# Fan.net
KiCad netlist of a schematic drawn in Altium Designer
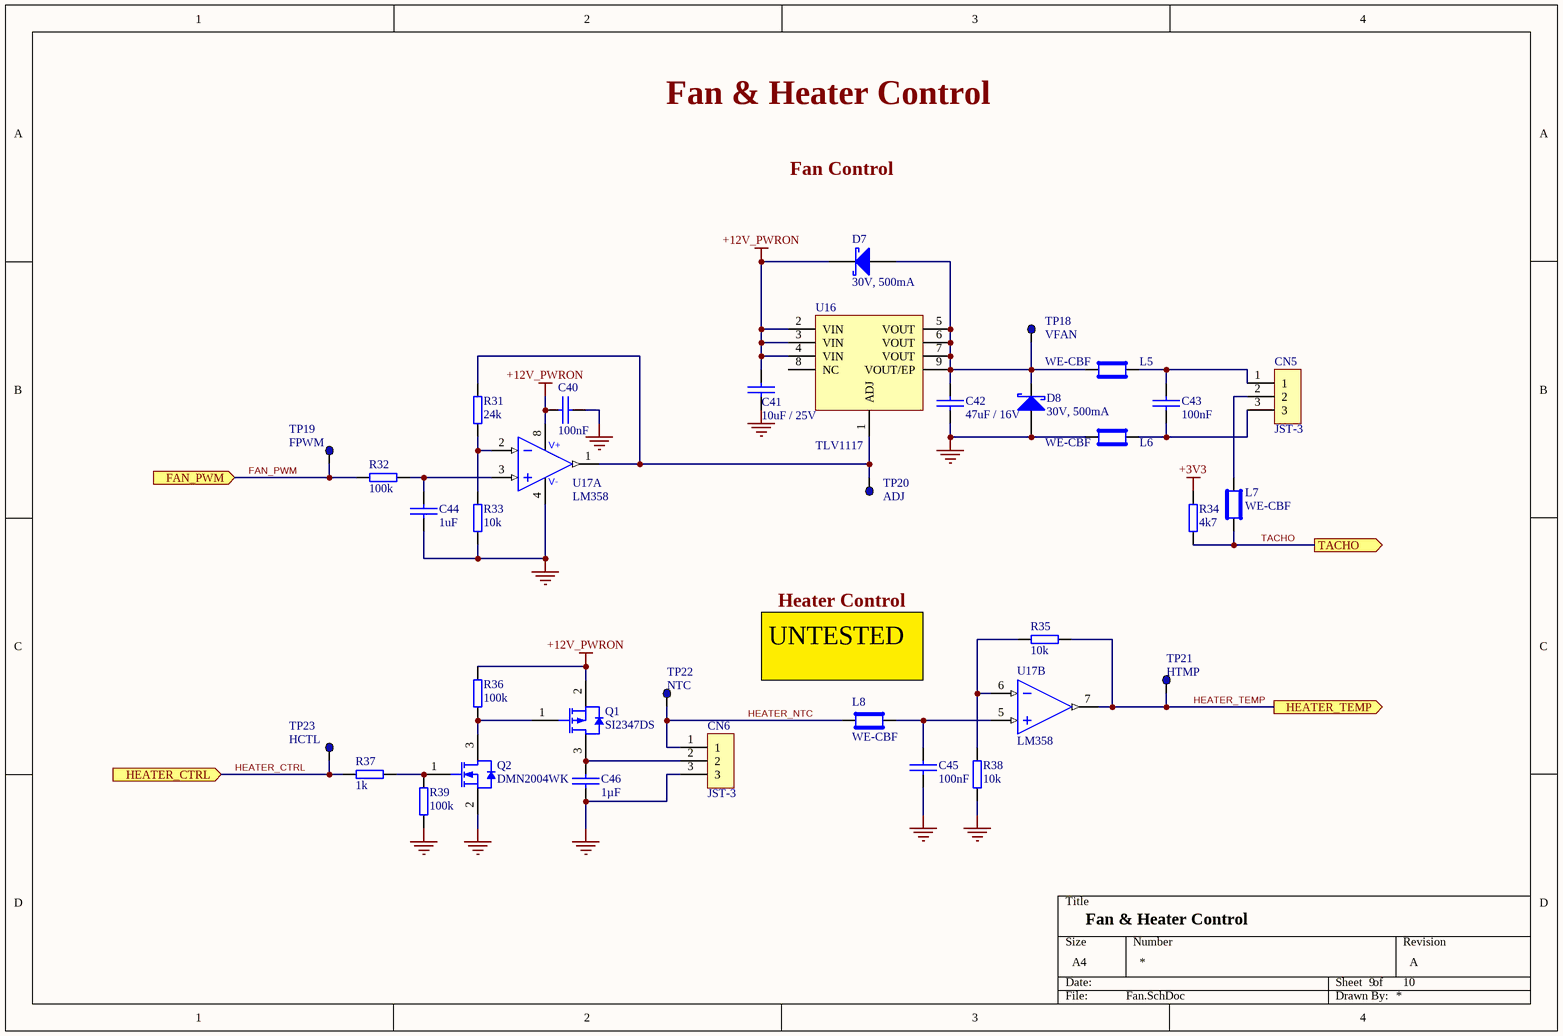
[diagram p0: Fan.SchDoc]

(export (version "E")
  (design (tool "Eeschema 10.0.6"))
  (components
    (comp (ref "C40")
      (value "100nF")
      (footprint "C0603")
      (description "CAP CER 0.1UF 50V X7R 0603")
      (fields (field (name "PART NUMBER") "C0603C104K5RACTU") (field (name "MANUFACTURER") "Kemet"))
      (libsource (lib "AKLib") (part "CAP"))
    )
    (comp (ref "C41")
      (value "10uF / 25V")
      (footprint "C0603")
      (description "CAP CER 10UF 25V X5R 0603")
      (fields
        (field (name "PART NUMBER") "ZRB18AR61E106ME01L")
        (field (name "MANUFACTURER") "Murata Electronics North America")
      )
      (libsource (lib "AKLib") (part "CAP"))
    )
    (comp (ref "C42")
      (value "47uF / 16V")
      (footprint "C1206")
      (description "CAP CER 47UF 16V X5R 1206")
      (fields
        (field (name "PART NUMBER") "C3216X5R1C476M160AB")
        (field (name "MANUFACTURER") "TDK Corporation")
      )
      (libsource (lib "AKLib") (part "CAP"))
    )
    (comp (ref "C43")
      (value "100nF")
      (footprint "C0603")
      (description "CAP CER 0.1UF 50V X7R 0603")
      (fields (field (name "PART NUMBER") "C0603C104K5RACTU") (field (name "MANUFACTURER") "Kemet"))
      (libsource (lib "AKLib") (part "CAP"))
    )
    (comp (ref "C44")
      (value "1uF")
      (footprint "C0603")
      (description "CAP CER 1UF 25V X7R 0603")
      (fields
        (field (name "PART NUMBER") "GCM188R71E105KA64D")
        (field (name "MANUFACTURER") "Murata Electronics North America")
      )
      (libsource (lib "AKLib") (part "CAP"))
    )
    (comp (ref "C45")
      (value "100nF")
      (footprint "C0603")
      (description "CAP CER 0.1UF 50V X7R 0603")
      (fields (field (name "PART NUMBER") "C0603C104K5RACTU") (field (name "MANUFACTURER") "Kemet"))
      (libsource (lib "AKLib") (part "CAP"))
    )
    (comp (ref "C46")
      (value "1µF")
      (footprint "C0805")
      (description "CAP CER 1UF 50V X7R 0805")
      (fields (field (name "PART NUMBER") "C0805C105K5RACTU") (field (name "MANUFACTURER") "Kemet"))
      (libsource (lib "AKLib") (part "CAP"))
    )
    (comp (ref "CN5")
      (value "JST-3")
      (footprint "JST-3")
      (description "CONN HEADER XH TOP 3POS 2.5MM")
      (fields
        (field (name "PART NUMBER") "B3B-XH-A(LF)(SN)")
        (field (name "MANUFACTURER") "JST Sales America Inc.")
      )
      (libsource (lib "AKLib") (part "Header 1x3"))
    )
    (comp (ref "CN6")
      (value "JST-3")
      (footprint "JST-3")
      (description "CONN HEADER XH TOP 3POS 2.5MM")
      (fields
        (field (name "PART NUMBER") "B3B-XH-A(LF)(SN)")
        (field (name "MANUFACTURER") "JST Sales America Inc.")
      )
      (libsource (lib "AKLib") (part "Header 1x3"))
    )
    (comp (ref "D7")
      (value "30V, 500mA")
      (footprint "SOD523_N")
      (description "DIODE SCHOTTKY 30V 500MA SC79-2")
      (fields
        (field (name "PART NUMBER") "BAS 3005B-02V H6327")
        (field (name "MANUFACTURER") "Infineon Technologies")
      )
      (libsource (lib "AKLib") (part "Schottky Diode"))
    )
    (comp (ref "D8")
      (value "30V, 500mA")
      (footprint "SOD523_N")
      (description "DIODE SCHOTTKY 30V 500MA SC79-2")
      (fields
        (field (name "PART NUMBER") "BAS 3005B-02V H6327")
        (field (name "MANUFACTURER") "Infineon Technologies")
      )
      (libsource (lib "AKLib") (part "Schottky Diode"))
    )
    (comp (ref "L5")
      (value "WE-CBF")
      (footprint "L0603")
      (description "FERRITE BEAD 600 OHM 0603 1LN")
      (fields (field (name "PART NUMBER") "742792651") (field (name "MANUFACTURER") "Wurth Electronics Inc."))
      (libsource (lib "AKLib") (part "FBEAD"))
    )
    (comp (ref "L6")
      (value "WE-CBF")
      (footprint "L0603")
      (description "FERRITE BEAD 600 OHM 0603 1LN")
      (fields (field (name "PART NUMBER") "742792651") (field (name "MANUFACTURER") "Wurth Electronics Inc."))
      (libsource (lib "AKLib") (part "FBEAD"))
    )
    (comp (ref "L7")
      (value "WE-CBF")
      (footprint "L0603")
      (description "FERRITE BEAD 600 OHM 0603 1LN")
      (fields (field (name "PART NUMBER") "742792651") (field (name "MANUFACTURER") "Wurth Electronics Inc."))
      (libsource (lib "AKLib") (part "FBEAD"))
    )
    (comp (ref "L8")
      (value "WE-CBF")
      (footprint "L0603")
      (description "FERRITE BEAD 600 OHM 0603 1LN")
      (fields (field (name "PART NUMBER") "742792651") (field (name "MANUFACTURER") "Wurth Electronics Inc."))
      (libsource (lib "AKLib") (part "FBEAD"))
    )
    (comp (ref "Q1")
      (value "SI2347DS")
      (footprint "SOT23-3_N")
      (description "MOSFET P-CH 30V 5A SOT-23")
      (fields (field (name "PART NUMBER") "SI2347DS-T1-GE3") (field (name "MANUFACTURER") "Vishay Siliconix"))
      (libsource (lib "AKLib") (part "PMOS-GSD-3"))
    )
    (comp (ref "Q2")
      (value "DMN2004WK")
      (footprint "SC-70")
      (description "MOSFET N-CH 20V 540MA SC70-3")
      (fields (field (name "PART NUMBER") "DMN2004WK-7") (field (name "MANUFACTURER") "Diodes Incorporated"))
      (libsource (lib "AKLib") (part "NMOS-GSD-3"))
    )
    (comp (ref "R31")
      (value "24k")
      (footprint "R0603")
      (description "RES SMD 24K OHM 1% 1/10W 0603")
      (fields (field (name "PART NUMBER") "RC0603FR-0724KL") (field (name "MANUFACTURER") "Yageo"))
      (libsource (lib "AKLib") (part "RES"))
    )
    (comp (ref "R32")
      (value "100k")
      (footprint "R0603")
      (description "RES SMD 100K OHM 1% 1/10W 0603")
      (fields (field (name "PART NUMBER") "RC0603FR-07100KL") (field (name "MANUFACTURER") "Yageo"))
      (libsource (lib "AKLib") (part "RES"))
    )
    (comp (ref "R33")
      (value "10k")
      (footprint "R0603")
      (description "RES SMD 10K OHM 1% 1/10W 0603")
      (fields (field (name "PART NUMBER") "RC0603FR-0710KL") (field (name "MANUFACTURER") "Yageo"))
      (libsource (lib "AKLib") (part "RES"))
    )
    (comp (ref "R34")
      (value "4k7")
      (footprint "R0603")
      (description "RES SMD 4.7K OHM 1% 1/10W 0603")
      (fields (field (name "PART NUMBER") "CRCW06034K70FKEA") (field (name "MANUFACTURER") "Vishay Dale"))
      (libsource (lib "AKLib") (part "RES"))
    )
    (comp (ref "R35")
      (value "10k")
      (footprint "R0603")
      (description "RES SMD 10K OHM 1% 1/10W 0603")
      (fields (field (name "PART NUMBER") "RC0603FR-0710KL") (field (name "MANUFACTURER") "Yageo"))
      (libsource (lib "AKLib") (part "RES"))
    )
    (comp (ref "R36")
      (value "100k")
      (footprint "R0603")
      (description "RES SMD 100K OHM 1% 1/10W 0603")
      (fields (field (name "PART NUMBER") "RC0603FR-07100KL") (field (name "MANUFACTURER") "Yageo"))
      (libsource (lib "AKLib") (part "RES"))
    )
    (comp (ref "R37")
      (value "1k")
      (footprint "R0603")
      (description "RES SMD 1K OHM 1% 1/10W 0603")
      (fields (field (name "PART NUMBER") "CRCW06031K00FKEA") (field (name "MANUFACTURER") "Vishay Dale"))
      (libsource (lib "AKLib") (part "RES"))
    )
    (comp (ref "R38")
      (value "10k")
      (footprint "R0603")
      (description "RES SMD 10K OHM 1% 1/10W 0603")
      (fields (field (name "PART NUMBER") "RC0603FR-0710KL") (field (name "MANUFACTURER") "Yageo"))
      (libsource (lib "AKLib") (part "RES"))
    )
    (comp (ref "R39")
      (value "100k")
      (footprint "R0603")
      (description "RES SMD 100K OHM 1% 1/10W 0603")
      (fields (field (name "PART NUMBER") "RC0603FR-07100KL") (field (name "MANUFACTURER") "Yageo"))
      (libsource (lib "AKLib") (part "RES"))
    )
    (comp (ref "TP18")
      (value "VFAN")
      (footprint "TP_1mm")
      (fields (field (name "PART NUMBER") "TP"))
      (libsource (lib "AKLib") (part "TP"))
    )
    (comp (ref "TP19")
      (value "FPWM")
      (footprint "TP_1mm")
      (fields (field (name "PART NUMBER") "TP"))
      (libsource (lib "AKLib") (part "TP"))
    )
    (comp (ref "TP20")
      (value "ADJ")
      (footprint "TP_1mm")
      (fields (field (name "PART NUMBER") "TP"))
      (libsource (lib "AKLib") (part "TP"))
    )
    (comp (ref "TP21")
      (value "HTMP")
      (footprint "TP_1mm")
      (fields (field (name "PART NUMBER") "TP"))
      (libsource (lib "AKLib") (part "TP"))
    )
    (comp (ref "TP22")
      (value "NTC")
      (footprint "TP_1mm")
      (fields (field (name "PART NUMBER") "TP"))
      (libsource (lib "AKLib") (part "TP"))
    )
    (comp (ref "TP23")
      (value "HCTL")
      (footprint "TP_1mm")
      (fields (field (name "PART NUMBER") "TP"))
      (libsource (lib "AKLib") (part "TP"))
    )
    (comp (ref "U16")
      (value "TLV1117")
      (footprint "QFN80P400X400X80_HS-9N")
      (description "IC REG LDO ADJ 0.8A 8SON")
      (fields (field (name "PART NUMBER") "TLV1117IDRJR") (field (name "MANUFACTURER") "Texas Instruments"))
      (libsource (lib "AKLib") (part "TLV1117DRJ"))
    )
    (comp (ref "U17")
      (value "LM358")
      (footprint "DFN 2x2_LM358")
      (description "IC OPAMP GP 1.1MHZ 8DFN")
      (fields (field (name "PART NUMBER") "LM358QT") (field (name "MANUFACTURER") "STMicroelectronics"))
      (libsource (lib "AKLib") (part "LM358"))
    )
  )
  (nets
    (net (code "1") (name "+3V3") (class "Default")
      (node (ref "R34") (pin "2") (pinfunction "2_2") (pintype "passive"))
    )
    (net (code "2") (name "+12V_PWRON") (class "Default")
      (node (ref "C40") (pin "1") (pinfunction "1_1") (pintype "passive"))
      (node (ref "C41") (pin "2") (pinfunction "2_2") (pintype "passive"))
      (node (ref "D7") (pin "2") (pinfunction "K_2") (pintype "passive"))
      (node (ref "Q1") (pin "2") (pinfunction "S_2") (pintype "passive"))
      (node (ref "R36") (pin "2") (pinfunction "2_2") (pintype "passive"))
      (node (ref "U16") (pin "2") (pinfunction "VIN_2") (pintype "power_in"))
      (node (ref "U16") (pin "3") (pinfunction "VIN_3") (pintype "power_in"))
      (node (ref "U16") (pin "4") (pinfunction "VIN_4") (pintype "power_in"))
      (node (ref "U17") (pin "8") (pinfunction "V+_8") (pintype "power_in"))
    )
    (net (code "3") (name "/FAN_PWM") (class "Default")
      (node (ref "R32") (pin "1") (pinfunction "1_1") (pintype "passive"))
      (node (ref "TP19") (pin "1") (pinfunction "1_1") (pintype "passive"))
    )
    (net (code "4") (name "/HEATER_CTRL") (class "Default")
      (node (ref "R37") (pin "2") (pinfunction "2_2") (pintype "passive"))
      (node (ref "TP23") (pin "1") (pinfunction "1_1") (pintype "passive"))
    )
    (net (code "5") (name "/HEATER_NTC") (class "Default")
      (node (ref "CN6") (pin "1") (pinfunction "1_1") (pintype "passive"))
      (node (ref "L8") (pin "1") (pinfunction "1_1") (pintype "passive"))
      (node (ref "TP22") (pin "1") (pinfunction "1_1") (pintype "passive"))
    )
    (net (code "6") (name "/HEATER_TEMP") (class "Default")
      (node (ref "R35") (pin "2") (pinfunction "2_2") (pintype "passive"))
      (node (ref "TP21") (pin "1") (pinfunction "1_1") (pintype "passive"))
      (node (ref "U17") (pin "7") (pinfunction "OUT_7") (pintype "output"))
    )
    (net (code "7") (name "/TACHO") (class "Default")
      (node (ref "L7") (pin "1") (pinfunction "1_1") (pintype "passive"))
      (node (ref "R34") (pin "1") (pinfunction "1_1") (pintype "passive"))
    )
    (net (code "8") (name "GND") (class "Default")
      (node (ref "C40") (pin "2") (pinfunction "2_2") (pintype "passive"))
      (node (ref "C41") (pin "1") (pinfunction "1_1") (pintype "passive"))
      (node (ref "C42") (pin "1") (pinfunction "1_1") (pintype "passive"))
      (node (ref "C44") (pin "1") (pinfunction "1_1") (pintype "passive"))
      (node (ref "C45") (pin "1") (pinfunction "1_1") (pintype "passive"))
      (node (ref "C46") (pin "1") (pinfunction "1_1") (pintype "passive"))
      (node (ref "CN6") (pin "3") (pinfunction "3_3") (pintype "passive"))
      (node (ref "D8") (pin "1") (pinfunction "A_1") (pintype "passive"))
      (node (ref "L6") (pin "1") (pinfunction "1_1") (pintype "passive"))
      (node (ref "Q2") (pin "2") (pinfunction "S_2") (pintype "passive"))
      (node (ref "R33") (pin "2") (pinfunction "2_2") (pintype "passive"))
      (node (ref "R38") (pin "1") (pinfunction "1_1") (pintype "passive"))
      (node (ref "R39") (pin "1") (pinfunction "1_1") (pintype "passive"))
      (node (ref "U17") (pin "4") (pinfunction "V-_4") (pintype "power_in"))
    )
    (net (code "9") (name "Net-(C43-Pad1)") (class "Default")
      (node (ref "C43") (pin "1") (pinfunction "1_1") (pintype "passive"))
      (node (ref "CN5") (pin "3") (pinfunction "3_3") (pintype "passive"))
      (node (ref "L6") (pin "2") (pinfunction "2_2") (pintype "passive"))
    )
    (net (code "10") (name "Net-(C43-Pad2)") (class "Default")
      (node (ref "C43") (pin "2") (pinfunction "2_2") (pintype "passive"))
      (node (ref "CN5") (pin "1") (pinfunction "1_1") (pintype "passive"))
      (node (ref "L5") (pin "2") (pinfunction "2_2") (pintype "passive"))
    )
    (net (code "11") (name "Net-(CN5-Pad2)") (class "Default")
      (node (ref "CN5") (pin "2") (pinfunction "2_2") (pintype "passive"))
      (node (ref "L7") (pin "2") (pinfunction "2_2") (pintype "passive"))
    )
    (net (code "12") (name "Net-(D7-A)") (class "Default")
      (node (ref "C42") (pin "2") (pinfunction "2_2") (pintype "passive"))
      (node (ref "D7") (pin "1") (pinfunction "A_1") (pintype "passive"))
      (node (ref "D8") (pin "2") (pinfunction "K_2") (pintype "passive"))
      (node (ref "L5") (pin "1") (pinfunction "1_1") (pintype "passive"))
      (node (ref "TP18") (pin "1") (pinfunction "1_1") (pintype "passive"))
      (node (ref "U16") (pin "5") (pinfunction "VOUT_5") (pintype "power_in"))
      (node (ref "U16") (pin "6") (pinfunction "VOUT_6") (pintype "power_in"))
      (node (ref "U16") (pin "7") (pinfunction "VOUT_7") (pintype "power_in"))
      (node (ref "U16") (pin "9") (pinfunction "VOUT/EP_9") (pintype "power_in"))
    )
    (net (code "13") (name "Net-(Q1-D)") (class "Default")
      (node (ref "C46") (pin "2") (pinfunction "2_2") (pintype "passive"))
      (node (ref "CN6") (pin "2") (pinfunction "2_2") (pintype "passive"))
      (node (ref "Q1") (pin "3") (pinfunction "D_3") (pintype "passive"))
    )
    (net (code "14") (name "Net-(Q1-G)") (class "Default")
      (node (ref "Q1") (pin "1") (pinfunction "G_1") (pintype "passive"))
      (node (ref "Q2") (pin "3") (pinfunction "D_3") (pintype "passive"))
      (node (ref "R36") (pin "1") (pinfunction "1_1") (pintype "passive"))
    )
    (net (code "15") (name "Net-(Q2-G)") (class "Default")
      (node (ref "Q2") (pin "1") (pinfunction "G_1") (pintype "passive"))
      (node (ref "R37") (pin "1") (pinfunction "1_1") (pintype "passive"))
      (node (ref "R39") (pin "2") (pinfunction "2_2") (pintype "passive"))
    )
    (net (code "16") (name "Net-(U16-ADJ)") (class "Default")
      (node (ref "R31") (pin "2") (pinfunction "2_2") (pintype "passive"))
      (node (ref "TP20") (pin "1") (pinfunction "1_1") (pintype "passive"))
      (node (ref "U16") (pin "1") (pinfunction "ADJ_1") (pintype "passive"))
      (node (ref "U17") (pin "1") (pinfunction "OUT_1") (pintype "output"))
    )
    (net (code "17") (name "Net-(U17A-IN+)") (class "Default")
      (node (ref "C44") (pin "2") (pinfunction "2_2") (pintype "passive"))
      (node (ref "R32") (pin "2") (pinfunction "2_2") (pintype "passive"))
      (node (ref "U17") (pin "3") (pinfunction "IN+_3") (pintype "input"))
    )
    (net (code "18") (name "Net-(U17A-IN-)") (class "Default")
      (node (ref "R31") (pin "1") (pinfunction "1_1") (pintype "passive"))
      (node (ref "R33") (pin "1") (pinfunction "1_1") (pintype "passive"))
      (node (ref "U17") (pin "2") (pinfunction "IN-_2") (pintype "input"))
    )
    (net (code "19") (name "Net-(U17B-IN+)") (class "Default")
      (node (ref "C45") (pin "2") (pinfunction "2_2") (pintype "passive"))
      (node (ref "L8") (pin "2") (pinfunction "2_2") (pintype "passive"))
      (node (ref "U17") (pin "5") (pinfunction "IN+_5") (pintype "input"))
    )
    (net (code "20") (name "Net-(U17B-IN-)") (class "Default")
      (node (ref "R35") (pin "1") (pinfunction "1_1") (pintype "passive"))
      (node (ref "R38") (pin "2") (pinfunction "2_2") (pintype "passive"))
      (node (ref "U17") (pin "6") (pinfunction "IN-_6") (pintype "input"))
    )
    (net (code "21") (name "unconnected-(U16-NC-Pad8)") (class "Default")
      (node (ref "U16") (pin "8") (pinfunction "NC_8") (pintype "passive"))
    )
  )
)
